# habitat.net
KiCad netlist of a schematic drawn in EAGLE
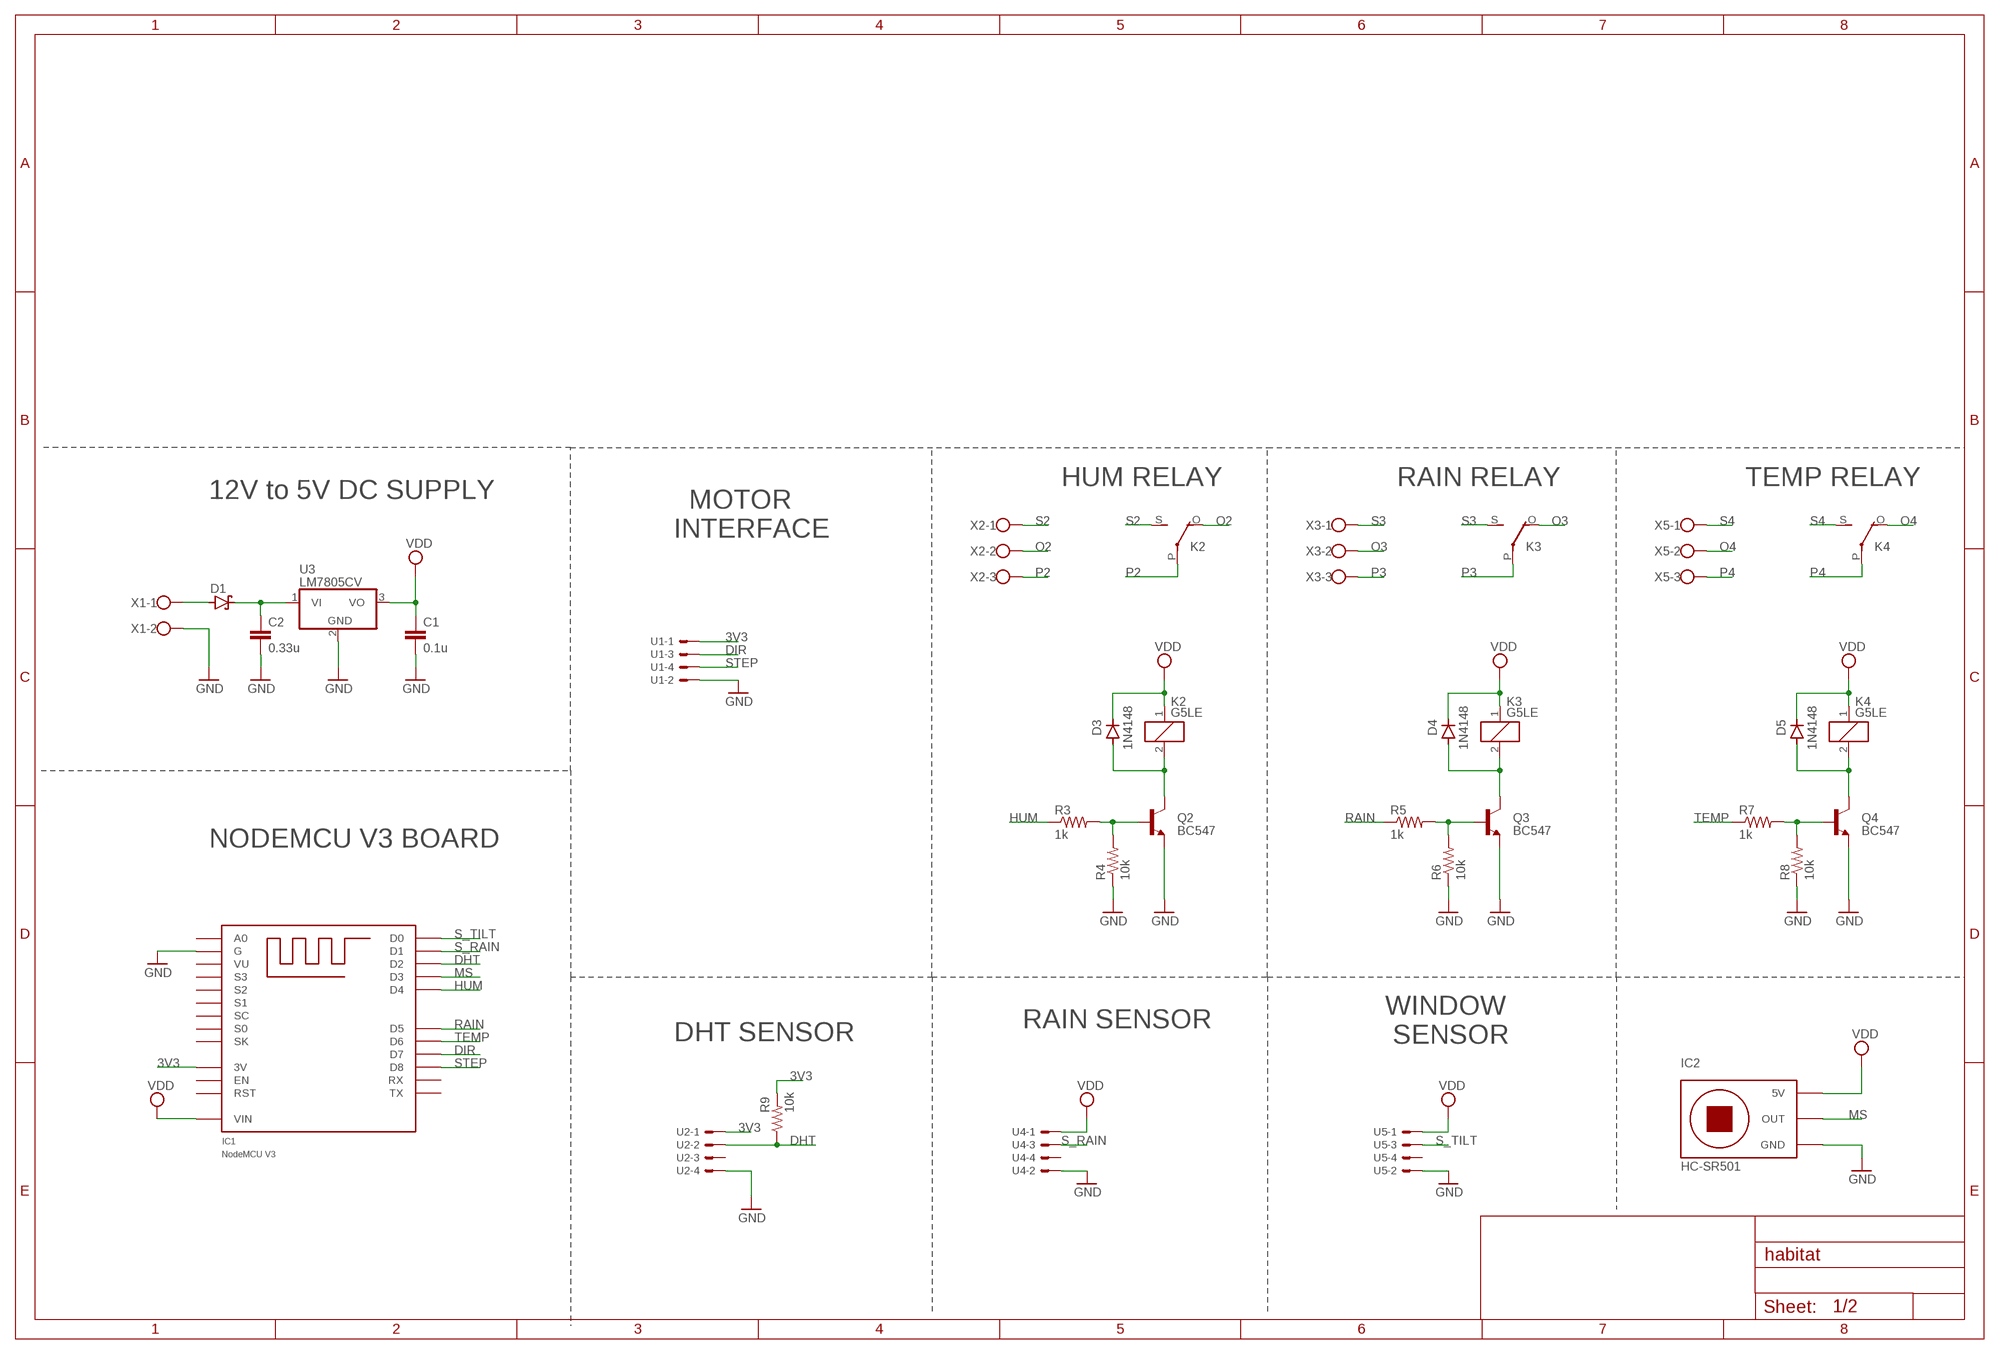
[diagram p0: schematic, sheet 1]

(export (version "E")
  (design (tool "Eeschema 10.0.6"))
  (components
    (comp (ref "C1")
      (value "0.1u")
      (footprint "eagle-import:C025-030X050")
      (libsource (lib "eagle-import") (part "C-EU025-030X050"))
    )
    (comp (ref "C2")
      (value "0.33u")
      (footprint "eagle-import:C025-030X050")
      (libsource (lib "eagle-import") (part "C-EU025-030X050"))
    )
    (comp (ref "D1")
      (value "1N5817-T")
      (footprint "eagle-import:DO41-7.6")
      (libsource (lib "eagle-import") (part "1N5817-T"))
    )
    (comp (ref "D3")
      (value "1N4148")
      (footprint "eagle-import:DO35-7")
      (libsource (lib "eagle-import") (part "1N4148DO35-7"))
    )
    (comp (ref "D4")
      (value "1N4148")
      (footprint "eagle-import:DO35-7")
      (libsource (lib "eagle-import") (part "1N4148DO35-7"))
    )
    (comp (ref "D5")
      (value "1N4148")
      (footprint "eagle-import:DO35-7")
      (libsource (lib "eagle-import") (part "1N4148DO35-7"))
    )
    (comp (ref "IC1")
      (value "NODEMCU_V3")
      (footprint "eagle-import:NODEMCU_V3")
      (libsource (lib "eagle-import") (part "NODEMCU_V3"))
    )
    (comp (ref "IC2")
      (value "HC-SR501")
      (footprint "eagle-import:HC-SR501")
      (libsource (lib "eagle-import") (part "HC-SR501"))
    )
    (comp (ref "K2")
      (value "G5LE")
      (footprint "eagle-import:G5LE")
      (libsource (lib "eagle-import") (part "G5LE"))
    )
    (comp (ref "K3")
      (value "G5LE")
      (footprint "eagle-import:G5LE")
      (libsource (lib "eagle-import") (part "G5LE"))
    )
    (comp (ref "K4")
      (value "G5LE")
      (footprint "eagle-import:G5LE")
      (libsource (lib "eagle-import") (part "G5LE"))
    )
    (comp (ref "Q2")
      (value "BC547")
      (footprint "eagle-import:TO92")
      (libsource (lib "eagle-import") (part "BC547"))
    )
    (comp (ref "Q3")
      (value "BC547")
      (footprint "eagle-import:TO92")
      (libsource (lib "eagle-import") (part "BC547"))
    )
    (comp (ref "Q4")
      (value "BC547")
      (footprint "eagle-import:TO92")
      (libsource (lib "eagle-import") (part "BC547"))
    )
    (comp (ref "R3")
      (value "1k")
      (footprint "eagle-import:0309_10")
      (libsource (lib "eagle-import") (part "R-US_0309/10"))
    )
    (comp (ref "R4")
      (value "10k")
      (footprint "eagle-import:0309_10")
      (libsource (lib "eagle-import") (part "R-US_0309/10"))
    )
    (comp (ref "R5")
      (value "1k")
      (footprint "eagle-import:0309_10")
      (libsource (lib "eagle-import") (part "R-US_0309/10"))
    )
    (comp (ref "R6")
      (value "10k")
      (footprint "eagle-import:0309_10")
      (libsource (lib "eagle-import") (part "R-US_0309/10"))
    )
    (comp (ref "R7")
      (value "1k")
      (footprint "eagle-import:0309_10")
      (libsource (lib "eagle-import") (part "R-US_0309/10"))
    )
    (comp (ref "R8")
      (value "10k")
      (footprint "eagle-import:0309_10")
      (libsource (lib "eagle-import") (part "R-US_0309/10"))
    )
    (comp (ref "R9")
      (value "10k")
      (footprint "eagle-import:0309_10")
      (libsource (lib "eagle-import") (part "R-US_0309/10"))
    )
    (comp (ref "U1")
      (value "KK-156-4")
      (footprint "eagle-import:KK-156-4")
      (fields (field (name "MF") "MOLEX"))
      (libsource (lib "eagle-import") (part "KK-156-4"))
    )
    (comp (ref "U2")
      (value "KK-156-4")
      (footprint "eagle-import:KK-156-4")
      (fields (field (name "MF") "MOLEX"))
      (libsource (lib "eagle-import") (part "KK-156-4"))
    )
    (comp (ref "U3")
      (value "LM7805CV")
      (footprint "eagle-import:TO220H")
      (libsource (lib "eagle-import") (part "78T05"))
    )
    (comp (ref "U4")
      (value "KK-156-4")
      (footprint "eagle-import:KK-156-4")
      (fields (field (name "MF") "MOLEX"))
      (libsource (lib "eagle-import") (part "KK-156-4"))
    )
    (comp (ref "U5")
      (value "KK-156-4")
      (footprint "eagle-import:KK-156-4")
      (fields (field (name "MF") "MOLEX"))
      (libsource (lib "eagle-import") (part "KK-156-4"))
    )
    (comp (ref "X1")
      (value "W237-102")
      (footprint "eagle-import:W237-102")
      (fields (field (name "MPN") "237-102"))
      (libsource (lib "eagle-import") (part "W237-102"))
    )
    (comp (ref "X2")
      (value "W237-103")
      (footprint "eagle-import:W237-103")
      (fields (field (name "MPN") "237-103"))
      (libsource (lib "eagle-import") (part "W237-103"))
    )
    (comp (ref "X3")
      (value "W237-103")
      (footprint "eagle-import:W237-103")
      (fields (field (name "MPN") "237-103"))
      (libsource (lib "eagle-import") (part "W237-103"))
    )
    (comp (ref "X5")
      (value "W237-103")
      (footprint "eagle-import:W237-103")
      (fields (field (name "MPN") "237-103"))
      (libsource (lib "eagle-import") (part "W237-103"))
    )
  )
  (nets
    (net (code "1") (name "3V3") (class "Default")
      (node (ref "IC1") (pin "P$11") (pinfunction "3V_P$11") (pintype "bidirectional"))
      (node (ref "IC1") (pin "P$16") (pinfunction "3V_P$16") (pintype "bidirectional"))
      (node (ref "IC1") (pin "P$25") (pinfunction "3V_P$25") (pintype "bidirectional"))
      (node (ref "R9") (pin "2") (pinfunction "2_2") (pintype "passive"))
      (node (ref "U1") (pin "1") (pinfunction "S_1") (pintype "passive"))
      (node (ref "U2") (pin "1") (pinfunction "S_1") (pintype "passive"))
    )
    (net (code "2") (name "DHT") (class "Default")
      (node (ref "IC1") (pin "P$28") (pinfunction "D2_P$28") (pintype "bidirectional"))
      (node (ref "R9") (pin "1") (pinfunction "1_1") (pintype "passive"))
      (node (ref "U2") (pin "2") (pinfunction "S_2") (pintype "passive"))
    )
    (net (code "3") (name "DIR") (class "Default")
      (node (ref "IC1") (pin "P$21") (pinfunction "D7_P$21") (pintype "bidirectional"))
      (node (ref "U1") (pin "3") (pinfunction "S_3") (pintype "passive"))
    )
    (net (code "4") (name "GND") (class "Default")
      (node (ref "C1") (pin "2") (pinfunction "2_2") (pintype "passive"))
      (node (ref "C2") (pin "2") (pinfunction "2_2") (pintype "passive"))
      (node (ref "IC1") (pin "P$10") (pinfunction "G_P$10") (pintype "bidirectional"))
      (node (ref "IC1") (pin "P$14") (pinfunction "G_P$14") (pintype "bidirectional"))
      (node (ref "IC1") (pin "P$17") (pinfunction "G_P$17") (pintype "bidirectional"))
      (node (ref "IC1") (pin "P$2") (pinfunction "G_P$2") (pintype "bidirectional"))
      (node (ref "IC1") (pin "P$24") (pinfunction "G_P$24") (pintype "bidirectional"))
      (node (ref "IC2") (pin "GND") (pinfunction "GND_GND") (pintype "bidirectional"))
      (node (ref "Q2") (pin "1") (pinfunction "E_1") (pintype "passive"))
      (node (ref "Q3") (pin "1") (pinfunction "E_1") (pintype "passive"))
      (node (ref "Q4") (pin "1") (pinfunction "E_1") (pintype "passive"))
      (node (ref "R4") (pin "1") (pinfunction "1_1") (pintype "passive"))
      (node (ref "R6") (pin "1") (pinfunction "1_1") (pintype "passive"))
      (node (ref "R8") (pin "1") (pinfunction "1_1") (pintype "passive"))
      (node (ref "U1") (pin "2") (pinfunction "S_2") (pintype "passive"))
      (node (ref "U2") (pin "4") (pinfunction "S_4") (pintype "passive"))
      (node (ref "U3") (pin "2") (pinfunction "GND_2") (pintype "passive"))
      (node (ref "U4") (pin "2") (pinfunction "S_2") (pintype "passive"))
      (node (ref "U5") (pin "2") (pinfunction "S_2") (pintype "passive"))
      (node (ref "X1") (pin "2") (pinfunction "KL_2") (pintype "passive"))
    )
    (net (code "5") (name "HUM") (class "Default")
      (node (ref "IC1") (pin "P$26") (pinfunction "D4_P$26") (pintype "bidirectional"))
      (node (ref "R3") (pin "1") (pinfunction "1_1") (pintype "passive"))
    )
    (net (code "6") (name "MS") (class "Default")
      (node (ref "IC1") (pin "P$27") (pinfunction "D3_P$27") (pintype "bidirectional"))
      (node (ref "IC2") (pin "OUT") (pinfunction "OUT_OUT") (pintype "bidirectional"))
    )
    (net (code "7") (name "Net-(Q2-B)") (class "Default")
      (node (ref "Q2") (pin "2") (pinfunction "B_2") (pintype "passive"))
      (node (ref "R3") (pin "2") (pinfunction "2_2") (pintype "passive"))
      (node (ref "R4") (pin "2") (pinfunction "2_2") (pintype "passive"))
    )
    (net (code "8") (name "Net-(Q2-C)") (class "Default")
      (node (ref "D3") (pin "A") (pinfunction "A_A") (pintype "passive"))
      (node (ref "K2") (pin "2") (pinfunction "2_2") (pintype "passive"))
      (node (ref "Q2") (pin "3") (pinfunction "C_3") (pintype "passive"))
    )
    (net (code "9") (name "Net-(Q3-B)") (class "Default")
      (node (ref "Q3") (pin "2") (pinfunction "B_2") (pintype "passive"))
      (node (ref "R5") (pin "2") (pinfunction "2_2") (pintype "passive"))
      (node (ref "R6") (pin "2") (pinfunction "2_2") (pintype "passive"))
    )
    (net (code "10") (name "Net-(Q3-C)") (class "Default")
      (node (ref "D4") (pin "A") (pinfunction "A_A") (pintype "passive"))
      (node (ref "K3") (pin "2") (pinfunction "2_2") (pintype "passive"))
      (node (ref "Q3") (pin "3") (pinfunction "C_3") (pintype "passive"))
    )
    (net (code "11") (name "Net-(Q4-B)") (class "Default")
      (node (ref "Q4") (pin "2") (pinfunction "B_2") (pintype "passive"))
      (node (ref "R7") (pin "2") (pinfunction "2_2") (pintype "passive"))
      (node (ref "R8") (pin "2") (pinfunction "2_2") (pintype "passive"))
    )
    (net (code "12") (name "Net-(Q4-C)") (class "Default")
      (node (ref "D5") (pin "A") (pinfunction "A_A") (pintype "passive"))
      (node (ref "K4") (pin "2") (pinfunction "2_2") (pintype "passive"))
      (node (ref "Q4") (pin "3") (pinfunction "C_3") (pintype "passive"))
    )
    (net (code "13") (name "Net-(U3-VI)") (class "Default")
      (node (ref "C2") (pin "1") (pinfunction "1_1") (pintype "passive"))
      (node (ref "D1") (pin "C") (pinfunction "C_C") (pintype "passive"))
      (node (ref "U3") (pin "1") (pinfunction "VI_1") (pintype "input"))
    )
    (net (code "14") (name "Net-(X1A-KL)") (class "Default")
      (node (ref "D1") (pin "A") (pinfunction "A_A") (pintype "passive"))
      (node (ref "X1") (pin "1") (pinfunction "KL_1") (pintype "passive"))
    )
    (net (code "15") (name "O2") (class "Default")
      (node (ref "K2") (pin "O") (pinfunction "O_O") (pintype "passive"))
      (node (ref "X2") (pin "2") (pinfunction "KL_2") (pintype "passive"))
    )
    (net (code "16") (name "O3") (class "Default")
      (node (ref "K3") (pin "O") (pinfunction "O_O") (pintype "passive"))
      (node (ref "X3") (pin "2") (pinfunction "KL_2") (pintype "passive"))
    )
    (net (code "17") (name "O4") (class "Default")
      (node (ref "K4") (pin "O") (pinfunction "O_O") (pintype "passive"))
      (node (ref "X5") (pin "2") (pinfunction "KL_2") (pintype "passive"))
    )
    (net (code "18") (name "P2") (class "Default")
      (node (ref "K2") (pin "P") (pinfunction "P_P") (pintype "passive"))
      (node (ref "X2") (pin "3") (pinfunction "KL_3") (pintype "passive"))
    )
    (net (code "19") (name "P3") (class "Default")
      (node (ref "K3") (pin "P") (pinfunction "P_P") (pintype "passive"))
      (node (ref "X3") (pin "3") (pinfunction "KL_3") (pintype "passive"))
    )
    (net (code "20") (name "P4") (class "Default")
      (node (ref "K4") (pin "P") (pinfunction "P_P") (pintype "passive"))
      (node (ref "X5") (pin "3") (pinfunction "KL_3") (pintype "passive"))
    )
    (net (code "21") (name "RAIN") (class "Default")
      (node (ref "IC1") (pin "P$23") (pinfunction "D5_P$23") (pintype "bidirectional"))
      (node (ref "R5") (pin "1") (pinfunction "1_1") (pintype "passive"))
    )
    (net (code "22") (name "S2") (class "Default")
      (node (ref "K2") (pin "S") (pinfunction "S_S") (pintype "passive"))
      (node (ref "X2") (pin "1") (pinfunction "KL_1") (pintype "passive"))
    )
    (net (code "23") (name "S3") (class "Default")
      (node (ref "K3") (pin "S") (pinfunction "S_S") (pintype "passive"))
      (node (ref "X3") (pin "1") (pinfunction "KL_1") (pintype "passive"))
    )
    (net (code "24") (name "S4") (class "Default")
      (node (ref "K4") (pin "S") (pinfunction "S_S") (pintype "passive"))
      (node (ref "X5") (pin "1") (pinfunction "KL_1") (pintype "passive"))
    )
    (net (code "25") (name "STEP") (class "Default")
      (node (ref "IC1") (pin "P$20") (pinfunction "D8_P$20") (pintype "bidirectional"))
      (node (ref "U1") (pin "4") (pinfunction "S_4") (pintype "passive"))
    )
    (net (code "26") (name "S_RAIN") (class "Default")
      (node (ref "IC1") (pin "P$29") (pinfunction "D1_P$29") (pintype "bidirectional"))
      (node (ref "U4") (pin "3") (pinfunction "S_3") (pintype "passive"))
    )
    (net (code "27") (name "S_TILT") (class "Default")
      (node (ref "IC1") (pin "P$30") (pinfunction "D0_P$30") (pintype "bidirectional"))
      (node (ref "U5") (pin "3") (pinfunction "S_3") (pintype "passive"))
    )
    (net (code "28") (name "TEMP") (class "Default")
      (node (ref "IC1") (pin "P$22") (pinfunction "D6_P$22") (pintype "bidirectional"))
      (node (ref "R7") (pin "1") (pinfunction "1_1") (pintype "passive"))
    )
    (net (code "29") (name "VDD") (class "Default")
      (node (ref "C1") (pin "1") (pinfunction "1_1") (pintype "passive"))
      (node (ref "D3") (pin "C") (pinfunction "C_C") (pintype "passive"))
      (node (ref "D4") (pin "C") (pinfunction "C_C") (pintype "passive"))
      (node (ref "D5") (pin "C") (pinfunction "C_C") (pintype "passive"))
      (node (ref "IC1") (pin "P$15") (pinfunction "VIN_P$15") (pintype "bidirectional"))
      (node (ref "IC2") (pin "VDD") (pinfunction "5V_VDD") (pintype "bidirectional"))
      (node (ref "K2") (pin "1") (pinfunction "1_1") (pintype "passive"))
      (node (ref "K3") (pin "1") (pinfunction "1_1") (pintype "passive"))
      (node (ref "K4") (pin "1") (pinfunction "1_1") (pintype "passive"))
      (node (ref "U3") (pin "3") (pinfunction "VO_3") (pintype "passive"))
      (node (ref "U4") (pin "1") (pinfunction "S_1") (pintype "passive"))
      (node (ref "U5") (pin "1") (pinfunction "S_1") (pintype "passive"))
    )
    (net (code "30") (name "unconnected-(IC1-A0-PadP$1)") (class "Default")
      (node (ref "IC1") (pin "P$1") (pinfunction "A0_P$1") (pintype "bidirectional"))
    )
    (net (code "31") (name "unconnected-(IC1-EN-PadP$12)") (class "Default")
      (node (ref "IC1") (pin "P$12") (pinfunction "EN_P$12") (pintype "bidirectional"))
    )
    (net (code "32") (name "unconnected-(IC1-RST-PadP$13)") (class "Default")
      (node (ref "IC1") (pin "P$13") (pinfunction "RST_P$13") (pintype "bidirectional"))
    )
    (net (code "33") (name "unconnected-(IC1-RX-PadP$19)") (class "Default")
      (node (ref "IC1") (pin "P$19") (pinfunction "RX_P$19") (pintype "bidirectional"))
    )
    (net (code "34") (name "unconnected-(IC1-S0-PadP$8)") (class "Default")
      (node (ref "IC1") (pin "P$8") (pinfunction "S0_P$8") (pintype "bidirectional"))
    )
    (net (code "35") (name "unconnected-(IC1-S1-PadP$6)") (class "Default")
      (node (ref "IC1") (pin "P$6") (pinfunction "S1_P$6") (pintype "bidirectional"))
    )
    (net (code "36") (name "unconnected-(IC1-S2-PadP$5)") (class "Default")
      (node (ref "IC1") (pin "P$5") (pinfunction "S2_P$5") (pintype "bidirectional"))
    )
    (net (code "37") (name "unconnected-(IC1-S3-PadP$4)") (class "Default")
      (node (ref "IC1") (pin "P$4") (pinfunction "S3_P$4") (pintype "bidirectional"))
    )
    (net (code "38") (name "unconnected-(IC1-SC-PadP$7)") (class "Default")
      (node (ref "IC1") (pin "P$7") (pinfunction "SC_P$7") (pintype "bidirectional"))
    )
    (net (code "39") (name "unconnected-(IC1-SK-PadP$9)") (class "Default")
      (node (ref "IC1") (pin "P$9") (pinfunction "SK_P$9") (pintype "bidirectional"))
    )
    (net (code "40") (name "unconnected-(IC1-TX-PadP$18)") (class "Default")
      (node (ref "IC1") (pin "P$18") (pinfunction "TX_P$18") (pintype "bidirectional"))
    )
    (net (code "41") (name "unconnected-(IC1-VU-PadP$3)") (class "Default")
      (node (ref "IC1") (pin "P$3") (pinfunction "VU_P$3") (pintype "bidirectional"))
    )
    (net (code "42") (name "unconnected-(U2C-S-Pad3)") (class "Default")
      (node (ref "U2") (pin "3") (pinfunction "S_3") (pintype "passive"))
    )
    (net (code "43") (name "unconnected-(U4D-S-Pad4)") (class "Default")
      (node (ref "U4") (pin "4") (pinfunction "S_4") (pintype "passive"))
    )
    (net (code "44") (name "unconnected-(U5D-S-Pad4)") (class "Default")
      (node (ref "U5") (pin "4") (pinfunction "S_4") (pintype "passive"))
    )
  )
)
